# Macropad.net
KiCad netlist of a schematic drawn in Altium Designer
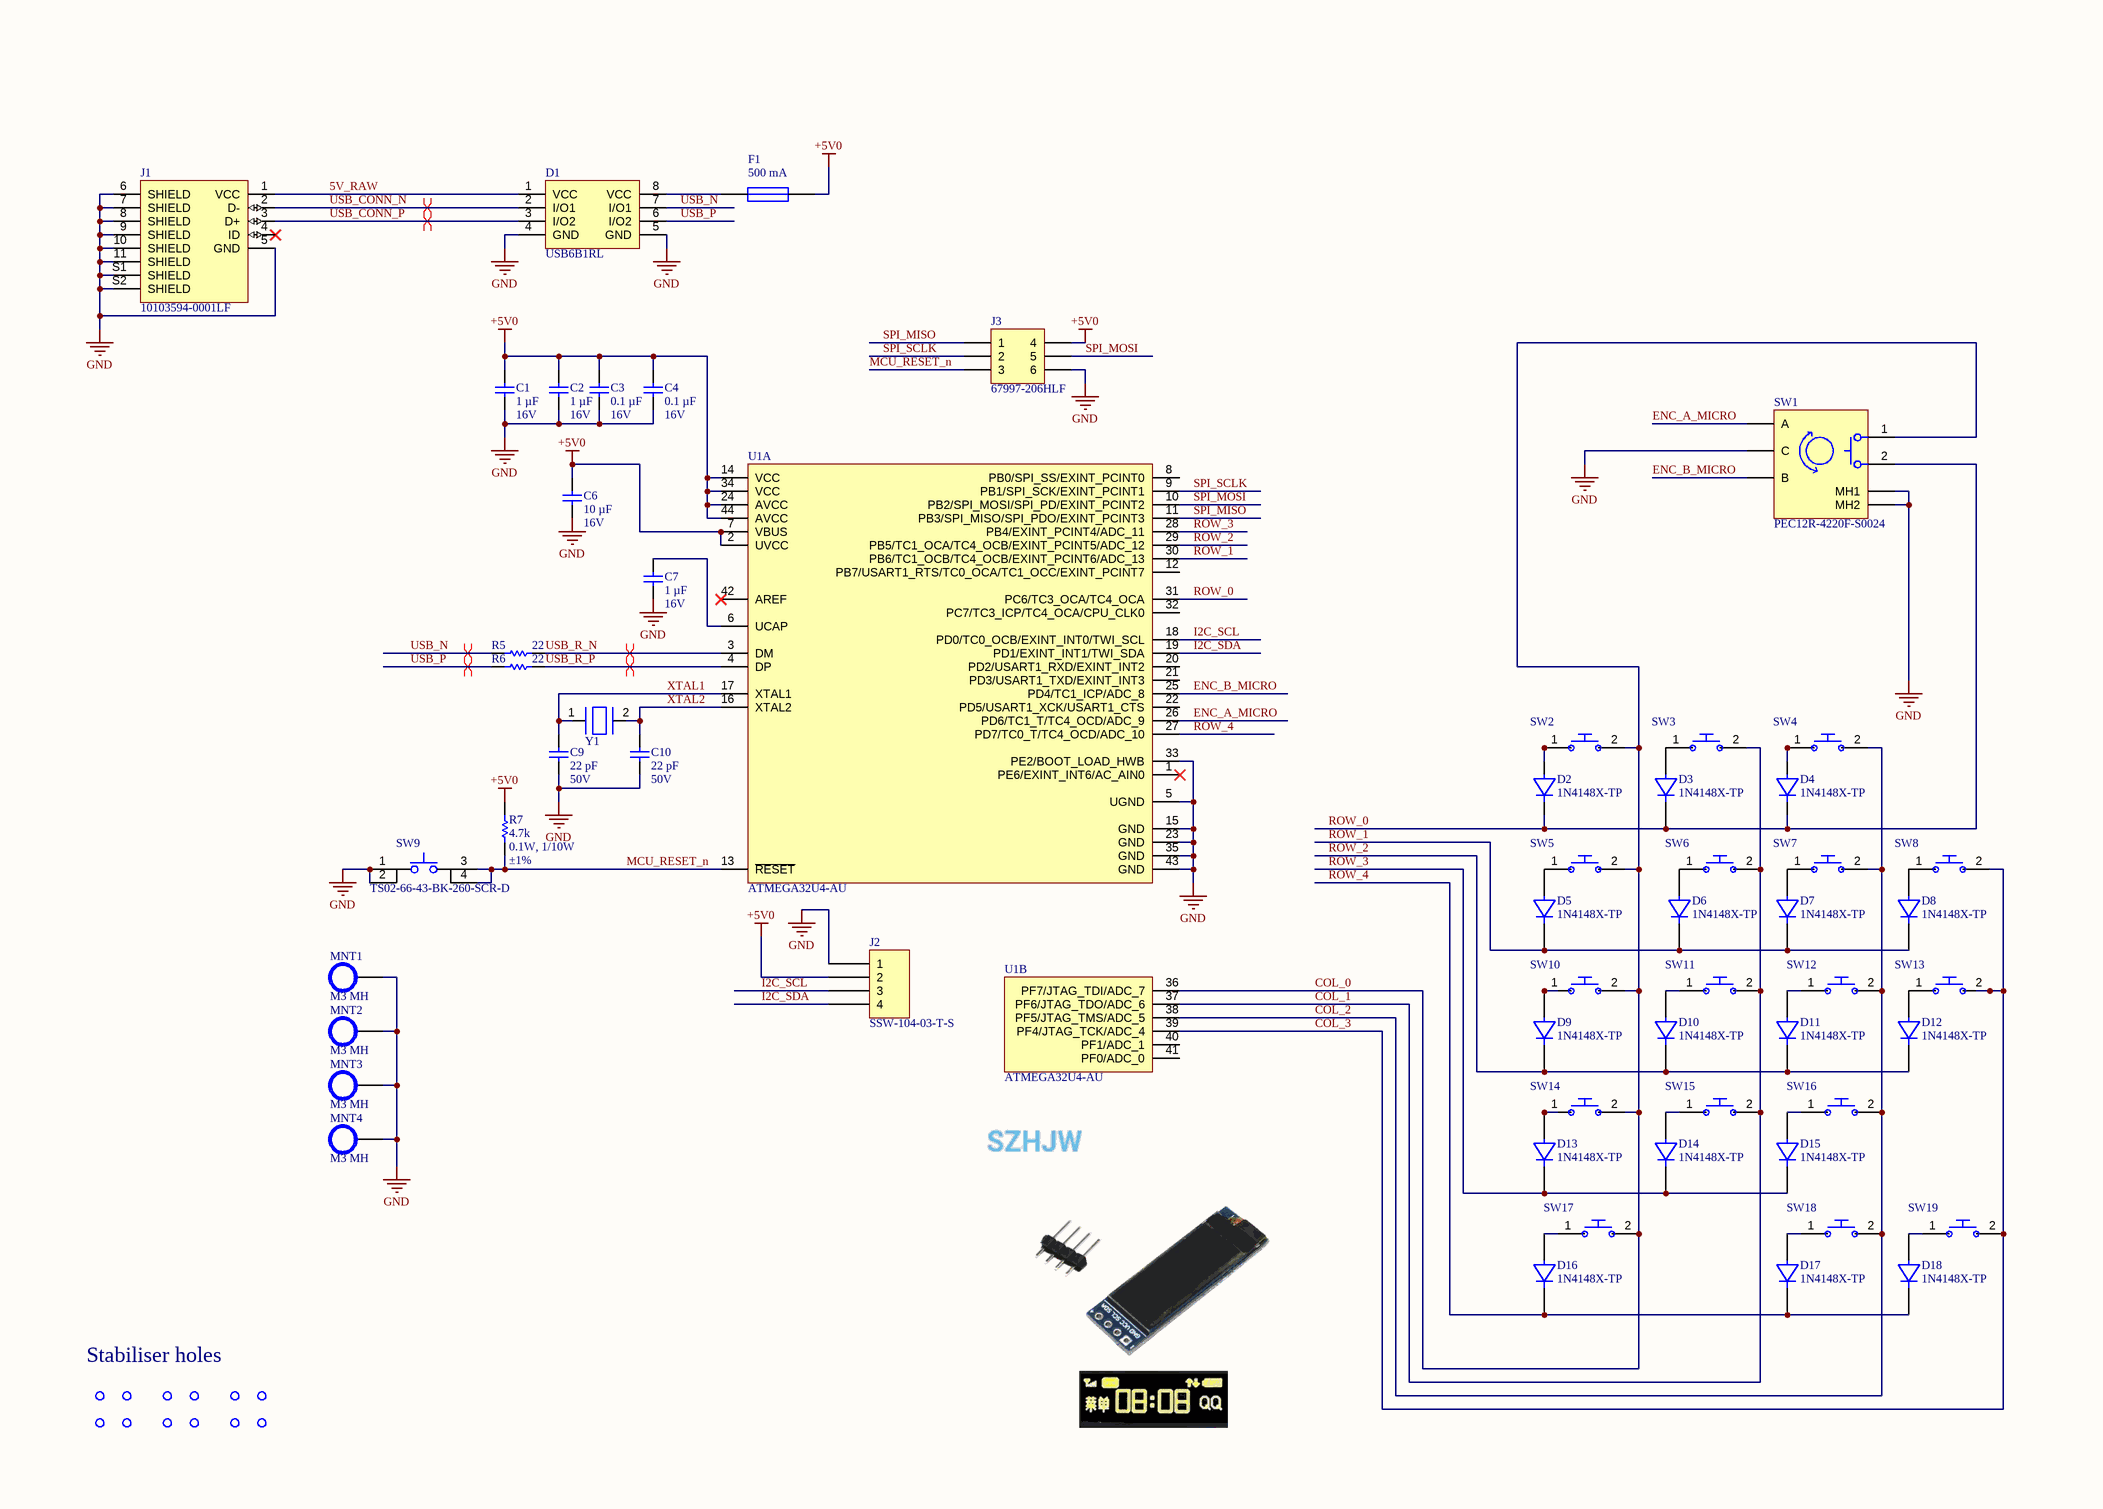
[diagram p0: Macropad.SchDoc]

(export (version "E")
  (design (tool "Eeschema 10.0.6"))
  (components
    (comp (ref "C1")
      (value "0603YC105KAT2A")
      (footprint "C_1608_0603")
      (description "CAP CER 1UF 16V X7R 0603")
      (fields
        (field (name "CAPACITANCE") "1 µF")
        (field (name "VOLTAGE RATING") "16V")
        (field (name "MANUFACTURER") "KYOCERA AVX")
        (field (name "TOLERANCE") "±10%")
      )
      (libsource (lib "adrianna-altium-lib") (part "C_NON_POLAR"))
    )
    (comp (ref "C2")
      (value "0603YC105KAT2A")
      (footprint "C_1608_0603")
      (description "CAP CER 1UF 16V X7R 0603")
      (fields
        (field (name "CAPACITANCE") "1 µF")
        (field (name "VOLTAGE RATING") "16V")
        (field (name "MANUFACTURER") "KYOCERA AVX")
        (field (name "TOLERANCE") "±10%")
      )
      (libsource (lib "adrianna-altium-lib") (part "C_NON_POLAR"))
    )
    (comp (ref "C3")
      (value "0603YC104KAT2A")
      (footprint "C_1608_0603")
      (description "CAP CER 0.1UF 16V X7R 0603")
      (fields
        (field (name "CAPACITANCE") "0.1 µF")
        (field (name "VOLTAGE RATING") "16V")
        (field (name "MANUFACTURER") "KYOCERA AVX")
        (field (name "TOLERANCE") "±10%")
      )
      (libsource (lib "adrianna-altium-lib") (part "C_NON_POLAR"))
    )
    (comp (ref "C4")
      (value "0603YC104KAT2A")
      (footprint "C_1608_0603")
      (description "CAP CER 0.1UF 16V X7R 0603")
      (fields
        (field (name "CAPACITANCE") "0.1 µF")
        (field (name "VOLTAGE RATING") "16V")
        (field (name "MANUFACTURER") "KYOCERA AVX")
        (field (name "TOLERANCE") "±10%")
      )
      (libsource (lib "adrianna-altium-lib") (part "C_NON_POLAR"))
    )
    (comp (ref "C6")
      (value "0805YC106KAT2A")
      (footprint "C_2012_0805")
      (description "CAP MLCC 10UF 16V 0805")
      (fields
        (field (name "CAPACITANCE") "10 µF")
        (field (name "VOLTAGE RATING") "16V")
        (field (name "MANUFACTURER") "KYOCERA AVX")
        (field (name "TOLERANCE") "±10%")
      )
      (libsource (lib "adrianna-altium-lib") (part "C_NON_POLAR"))
    )
    (comp (ref "C7")
      (value "0603YC105KAT2A")
      (footprint "C_1608_0603")
      (description "CAP CER 1UF 16V X7R 0603")
      (fields
        (field (name "CAPACITANCE") "1 µF")
        (field (name "VOLTAGE RATING") "16V")
        (field (name "MANUFACTURER") "KYOCERA AVX")
        (field (name "TOLERANCE") "±10%")
      )
      (libsource (lib "adrianna-altium-lib") (part "C_NON_POLAR"))
    )
    (comp (ref "C9")
      (value "06035A220JAT2A")
      (footprint "C_1608_0603")
      (description "CAP CER 22PF 50V C0G/NP0 0603")
      (fields
        (field (name "CAPACITANCE") "22 pF")
        (field (name "VOLTAGE RATING") "50V")
        (field (name "MANUFACTURER") "KYOCERA AVX")
        (field (name "TOLERANCE") "±5%")
      )
      (libsource (lib "adrianna-altium-lib") (part "C_NON_POLAR"))
    )
    (comp (ref "C10")
      (value "06035A220JAT2A")
      (footprint "C_1608_0603")
      (description "CAP CER 22PF 50V C0G/NP0 0603")
      (fields
        (field (name "CAPACITANCE") "22 pF")
        (field (name "VOLTAGE RATING") "50V")
        (field (name "MANUFACTURER") "KYOCERA AVX")
        (field (name "TOLERANCE") "±5%")
      )
      (libsource (lib "adrianna-altium-lib") (part "C_NON_POLAR"))
    )
    (comp (ref "D1")
      (value "USB6B1RL")
      (footprint "SOIC_8_1270_4900X3900X1750_ST_SO-8")
      (description "TVS DIODE 5.25VWM 8-SO")
      (fields (field (name "PN") "USB6B1RL") (field (name "MANUFACTURER") "STMicroelectronics"))
      (libsource (lib "adrianna-altium-lib") (part "D_TVS_USB6B1"))
    )
    (comp (ref "D2")
      (value "1N4148X-TP")
      (footprint "D_MCC_SOD-523")
      (description "DIODE GEN PURP 75V 150MA SOD523")
      (fields (field (name "MANUFACTURER") "Micro Commercial Co"))
      (libsource (lib "adrianna-altium-lib") (part "D_DIODE_KA"))
    )
    (comp (ref "D3")
      (value "1N4148X-TP")
      (footprint "D_MCC_SOD-523")
      (description "DIODE GEN PURP 75V 150MA SOD523")
      (fields (field (name "MANUFACTURER") "Micro Commercial Co"))
      (libsource (lib "adrianna-altium-lib") (part "D_DIODE_KA"))
    )
    (comp (ref "D4")
      (value "1N4148X-TP")
      (footprint "D_MCC_SOD-523")
      (description "DIODE GEN PURP 75V 150MA SOD523")
      (fields (field (name "MANUFACTURER") "Micro Commercial Co"))
      (libsource (lib "adrianna-altium-lib") (part "D_DIODE_KA"))
    )
    (comp (ref "D5")
      (value "1N4148X-TP")
      (footprint "D_MCC_SOD-523")
      (description "DIODE GEN PURP 75V 150MA SOD523")
      (fields (field (name "MANUFACTURER") "Micro Commercial Co"))
      (libsource (lib "adrianna-altium-lib") (part "D_DIODE_KA"))
    )
    (comp (ref "D6")
      (value "1N4148X-TP")
      (footprint "D_MCC_SOD-523")
      (description "DIODE GEN PURP 75V 150MA SOD523")
      (fields (field (name "MANUFACTURER") "Micro Commercial Co"))
      (libsource (lib "adrianna-altium-lib") (part "D_DIODE_KA"))
    )
    (comp (ref "D7")
      (value "1N4148X-TP")
      (footprint "D_MCC_SOD-523")
      (description "DIODE GEN PURP 75V 150MA SOD523")
      (fields (field (name "MANUFACTURER") "Micro Commercial Co"))
      (libsource (lib "adrianna-altium-lib") (part "D_DIODE_KA"))
    )
    (comp (ref "D8")
      (value "1N4148X-TP")
      (footprint "D_MCC_SOD-523")
      (description "DIODE GEN PURP 75V 150MA SOD523")
      (fields (field (name "MANUFACTURER") "Micro Commercial Co"))
      (libsource (lib "adrianna-altium-lib") (part "D_DIODE_KA"))
    )
    (comp (ref "D9")
      (value "1N4148X-TP")
      (footprint "D_MCC_SOD-523")
      (description "DIODE GEN PURP 75V 150MA SOD523")
      (fields (field (name "MANUFACTURER") "Micro Commercial Co"))
      (libsource (lib "adrianna-altium-lib") (part "D_DIODE_KA"))
    )
    (comp (ref "D10")
      (value "1N4148X-TP")
      (footprint "D_MCC_SOD-523")
      (description "DIODE GEN PURP 75V 150MA SOD523")
      (fields (field (name "MANUFACTURER") "Micro Commercial Co"))
      (libsource (lib "adrianna-altium-lib") (part "D_DIODE_KA"))
    )
    (comp (ref "D11")
      (value "1N4148X-TP")
      (footprint "D_MCC_SOD-523")
      (description "DIODE GEN PURP 75V 150MA SOD523")
      (fields (field (name "MANUFACTURER") "Micro Commercial Co"))
      (libsource (lib "adrianna-altium-lib") (part "D_DIODE_KA"))
    )
    (comp (ref "D12")
      (value "1N4148X-TP")
      (footprint "D_MCC_SOD-523")
      (description "DIODE GEN PURP 75V 150MA SOD523")
      (fields (field (name "MANUFACTURER") "Micro Commercial Co"))
      (libsource (lib "adrianna-altium-lib") (part "D_DIODE_KA"))
    )
    (comp (ref "D13")
      (value "1N4148X-TP")
      (footprint "D_MCC_SOD-523")
      (description "DIODE GEN PURP 75V 150MA SOD523")
      (fields (field (name "MANUFACTURER") "Micro Commercial Co"))
      (libsource (lib "adrianna-altium-lib") (part "D_DIODE_KA"))
    )
    (comp (ref "D14")
      (value "1N4148X-TP")
      (footprint "D_MCC_SOD-523")
      (description "DIODE GEN PURP 75V 150MA SOD523")
      (fields (field (name "MANUFACTURER") "Micro Commercial Co"))
      (libsource (lib "adrianna-altium-lib") (part "D_DIODE_KA"))
    )
    (comp (ref "D15")
      (value "1N4148X-TP")
      (footprint "D_MCC_SOD-523")
      (description "DIODE GEN PURP 75V 150MA SOD523")
      (fields (field (name "MANUFACTURER") "Micro Commercial Co"))
      (libsource (lib "adrianna-altium-lib") (part "D_DIODE_KA"))
    )
    (comp (ref "D16")
      (value "1N4148X-TP")
      (footprint "D_MCC_SOD-523")
      (description "DIODE GEN PURP 75V 150MA SOD523")
      (fields (field (name "MANUFACTURER") "Micro Commercial Co"))
      (libsource (lib "adrianna-altium-lib") (part "D_DIODE_KA"))
    )
    (comp (ref "D17")
      (value "1N4148X-TP")
      (footprint "D_MCC_SOD-523")
      (description "DIODE GEN PURP 75V 150MA SOD523")
      (fields (field (name "MANUFACTURER") "Micro Commercial Co"))
      (libsource (lib "adrianna-altium-lib") (part "D_DIODE_KA"))
    )
    (comp (ref "D18")
      (value "1N4148X-TP")
      (footprint "D_MCC_SOD-523")
      (description "DIODE GEN PURP 75V 150MA SOD523")
      (fields (field (name "MANUFACTURER") "Micro Commercial Co"))
      (libsource (lib "adrianna-altium-lib") (part "D_DIODE_KA"))
    )
    (comp (ref "F1")
      (value "0ZCK0050FF2E")
      (footprint "FUSE_2012_0805_BELFUSE")
      (description "PTC RESET FUSE 6V 500MA 0805")
      (fields (field (name "MANUFACTURER") "Bel Fuse Inc.") (field (name "CURRENT RATING") "500 mA"))
      (libsource (lib "adrianna-altium-lib") (part "F_FUSE"))
    )
    (comp (ref "J1")
      (value "10103594-0001LF")
      (footprint "CONN_10103594-0001LF")
      (description "CONN RCPT USB2.0 MICRO B SMD R/A")
      (fields (field (name "PN") "10103594-0001LF") (field (name "MANUFACTURER") "Amphenol ICC (FCI)"))
      (libsource (lib "adrianna-altium-lib") (part "J_CONN_MICRO-USB"))
    )
    (comp (ref "J2")
      (value "SSW-104-03-T-S")
      (footprint "SAMTEC SSW-104-03-T-S")
      (description "CONN RCPT 4POS 0.1 TIN PCB")
      (fields (field (name "MANUFACTURER") "Samtec Inc."))
      (libsource (lib "Celestial Altium Library - altium_library") (part "4 Pin"))
    )
    (comp (ref "J3")
      (value "67997-206HLF")
      (footprint "CONN_2X3_HDR_2540")
      (description "CONN HEADER VERT 6POS 2.54MM")
      (fields (field (name "PN") "67997-206HLF") (field (name "MANUFACTURER") "Amphenol ICC (FCI)"))
      (libsource (lib "adrianna-altium-lib") (part "J_HDR_2X3"))
    )
    (comp (ref "MNT1")
      (value "M3 Mounting Hole")
      (footprint "MH_M3_PTH_VIA-SPOKES")
      (fields (field (name "DISPLAY NAME") "M3 MH"))
      (libsource (lib "adrianna-altium-lib") (part "MH_M3"))
    )
    (comp (ref "MNT2")
      (value "M3 Mounting Hole")
      (footprint "MH_M3_PTH_VIA-SPOKES")
      (fields (field (name "DISPLAY NAME") "M3 MH"))
      (libsource (lib "adrianna-altium-lib") (part "MH_M3"))
    )
    (comp (ref "MNT3")
      (value "M3 Mounting Hole")
      (footprint "MH_M3_PTH_VIA-SPOKES")
      (fields (field (name "DISPLAY NAME") "M3 MH"))
      (libsource (lib "adrianna-altium-lib") (part "MH_M3"))
    )
    (comp (ref "MNT4")
      (value "M3 Mounting Hole")
      (footprint "MH_M3_PTH_VIA-SPOKES")
      (fields (field (name "DISPLAY NAME") "M3 MH"))
      (libsource (lib "adrianna-altium-lib") (part "MH_M3"))
    )
    (comp (ref "R5")
      (value "RMCF0603FT22R0")
      (footprint "R_1608_0603")
      (description "RES 22 OHM 1% 1/10W 0603")
      (fields
        (field (name "RESISTANCE") "22")
        (field (name "MANUFACTURER") "Stackpole Electronics Inc")
        (field (name "TOLERANCE") "±1%")
      )
      (libsource (lib "adrianna-altium-lib") (part "R_RESISTOR"))
    )
    (comp (ref "R6")
      (value "RMCF0603FT22R0")
      (footprint "R_1608_0603")
      (description "RES 22 OHM 1% 1/10W 0603")
      (fields
        (field (name "RESISTANCE") "22")
        (field (name "MANUFACTURER") "Stackpole Electronics Inc")
        (field (name "TOLERANCE") "±1%")
      )
      (libsource (lib "adrianna-altium-lib") (part "R_RESISTOR"))
    )
    (comp (ref "R7")
      (value "RMCF0603FT4K70")
      (footprint "R_1608_0603")
      (description "RES 4.7K OHM 1% 1/10W 0603")
      (fields
        (field (name "RESISTANCE") "4.7k")
        (field (name "POWER RATING") "0.1W, 1/10W")
        (field (name "MANUFACTURER") "Stackpole Electronics Inc")
        (field (name "TOLERANCE") "±1%")
      )
      (libsource (lib "adrianna-altium-lib") (part "R_RESISTOR"))
    )
    (comp (ref "STAB1")
      (value "Cherry Stabiliser Hole")
      (footprint "HOLE_CHERRY_STAB")
      (libsource (lib "adrianna-altium-lib") (part "HOLE_4"))
    )
    (comp (ref "STAB2")
      (value "Cherry Stabiliser Hole")
      (footprint "HOLE_CHERRY_STAB")
      (libsource (lib "adrianna-altium-lib") (part "HOLE_4"))
    )
    (comp (ref "STAB3")
      (value "Cherry Stabiliser Hole")
      (footprint "HOLE_CHERRY_STAB")
      (libsource (lib "adrianna-altium-lib") (part "HOLE_4"))
    )
    (comp (ref "SW1")
      (value "PEC12R-4220F-S0024")
      (footprint "SW_ENCODER_PEC12R-4220F-S0024")
      (description "ROTARY ENCODER MECHANICAL 24PPR")
      (fields (field (name "MANUFACTURER") "Bourns Inc."))
      (libsource (lib "adrianna-altium-lib") (part "SW_ENCODER_PEC12R-4220F-S0024"))
    )
    (comp (ref "SW2")
      (value "MX-Style Switch")
      (footprint "SW_CHERRY-MX-STYLE")
      (libsource (lib "adrianna-altium-lib") (part "SW_TACTILE_2POS"))
    )
    (comp (ref "SW3")
      (value "MX-Style Switch")
      (footprint "SW_CHERRY-MX-STYLE")
      (libsource (lib "adrianna-altium-lib") (part "SW_TACTILE_2POS"))
    )
    (comp (ref "SW4")
      (value "MX-Style Switch")
      (footprint "SW_CHERRY-MX-STYLE")
      (libsource (lib "adrianna-altium-lib") (part "SW_TACTILE_2POS"))
    )
    (comp (ref "SW5")
      (value "MX-Style Switch")
      (footprint "SW_CHERRY-MX-STYLE")
      (libsource (lib "adrianna-altium-lib") (part "SW_TACTILE_2POS"))
    )
    (comp (ref "SW6")
      (value "MX-Style Switch")
      (footprint "SW_CHERRY-MX-STYLE")
      (libsource (lib "adrianna-altium-lib") (part "SW_TACTILE_2POS"))
    )
    (comp (ref "SW7")
      (value "MX-Style Switch")
      (footprint "SW_CHERRY-MX-STYLE")
      (libsource (lib "adrianna-altium-lib") (part "SW_TACTILE_2POS"))
    )
    (comp (ref "SW8")
      (value "MX-Style Switch")
      (footprint "SW_CHERRY-MX-STYLE")
      (libsource (lib "adrianna-altium-lib") (part "SW_TACTILE_2POS"))
    )
    (comp (ref "SW9")
      (value "TS02-66-43-BK-260-SCR-D")
      (footprint "TS02-66-43-BK-260-SCR-D")
      (libsource (lib "Macropad") (part "TS02-66-43-BK-260-SCR-D"))
    )
    (comp (ref "SW10")
      (value "MX-Style Switch")
      (footprint "SW_CHERRY-MX-STYLE")
      (libsource (lib "adrianna-altium-lib") (part "SW_TACTILE_2POS"))
    )
    (comp (ref "SW11")
      (value "MX-Style Switch")
      (footprint "SW_CHERRY-MX-STYLE")
      (libsource (lib "adrianna-altium-lib") (part "SW_TACTILE_2POS"))
    )
    (comp (ref "SW12")
      (value "MX-Style Switch")
      (footprint "SW_CHERRY-MX-STYLE")
      (libsource (lib "adrianna-altium-lib") (part "SW_TACTILE_2POS"))
    )
    (comp (ref "SW13")
      (value "MX-Style Switch")
      (footprint "SW_CHERRY-MX-STYLE")
      (libsource (lib "adrianna-altium-lib") (part "SW_TACTILE_2POS"))
    )
    (comp (ref "SW14")
      (value "MX-Style Switch")
      (footprint "SW_CHERRY-MX-STYLE")
      (libsource (lib "adrianna-altium-lib") (part "SW_TACTILE_2POS"))
    )
    (comp (ref "SW15")
      (value "MX-Style Switch")
      (footprint "SW_CHERRY-MX-STYLE")
      (libsource (lib "adrianna-altium-lib") (part "SW_TACTILE_2POS"))
    )
    (comp (ref "SW16")
      (value "MX-Style Switch")
      (footprint "SW_CHERRY-MX-STYLE")
      (libsource (lib "adrianna-altium-lib") (part "SW_TACTILE_2POS"))
    )
    (comp (ref "SW17")
      (value "MX-Style Switch")
      (footprint "SW_CHERRY-MX-STYLE")
      (libsource (lib "adrianna-altium-lib") (part "SW_TACTILE_2POS"))
    )
    (comp (ref "SW18")
      (value "MX-Style Switch")
      (footprint "SW_CHERRY-MX-STYLE")
      (libsource (lib "adrianna-altium-lib") (part "SW_TACTILE_2POS"))
    )
    (comp (ref "SW19")
      (value "MX-Style Switch")
      (footprint "SW_CHERRY-MX-STYLE")
      (libsource (lib "adrianna-altium-lib") (part "SW_TACTILE_2POS"))
    )
    (comp (ref "U1")
      (value "ATMEGA32U4-AU")
      (footprint "QFP_44_800_1200X1200X120_ATMEL")
      (description "IC MCU 8BIT 32KB FLASH 44TQFP")
      (fields (field (name "MANUFACTURER") "Microchip Technology"))
      (libsource (lib "adrianna-altium-lib") (part "U_MCU_ATMEGA32U4"))
    )
    (comp (ref "Y1")
      (value "830036034")
      (footprint "Y_XTAL_HC49")
      (description "WE-XTAL QUARTZ CRYSTAL 16.0 MHZ;")
      (fields (field (name "MANUFACTURER") "Würth Elektronik"))
      (libsource (lib "adrianna-altium-lib") (part "Y_XTAL_X1X2"))
    )
  )
  (nets
    (net (code "1") (name "+5V0") (class "Default")
      (node (ref "C1") (pin "2") (pinfunction "2_2") (pintype "passive"))
      (node (ref "C2") (pin "2") (pinfunction "2_2") (pintype "passive"))
      (node (ref "C3") (pin "2") (pinfunction "2_2") (pintype "passive"))
      (node (ref "C4") (pin "2") (pinfunction "2_2") (pintype "passive"))
      (node (ref "C6") (pin "2") (pinfunction "2_2") (pintype "passive"))
      (node (ref "F1") (pin "2") (pinfunction "2_2") (pintype "passive"))
      (node (ref "J2") (pin "2") (pinfunction "2_2") (pintype "passive"))
      (node (ref "J3") (pin "4") (pinfunction "4_4") (pintype "passive"))
      (node (ref "R7") (pin "2") (pinfunction "2_2") (pintype "passive"))
      (node (ref "U1") (pin "14") (pinfunction "VCC_14") (pintype "passive"))
      (node (ref "U1") (pin "2") (pinfunction "UVCC_2") (pintype "passive"))
      (node (ref "U1") (pin "24") (pinfunction "AVCC_24") (pintype "passive"))
      (node (ref "U1") (pin "34") (pinfunction "VCC_34") (pintype "passive"))
      (node (ref "U1") (pin "44") (pinfunction "AVCC_44") (pintype "passive"))
      (node (ref "U1") (pin "7") (pinfunction "VBUS_7") (pintype "passive"))
    )
    (net (code "2") (name "/5V_RAW") (class "Default")
      (node (ref "D1") (pin "1") (pinfunction "VCC_1") (pintype "passive"))
      (node (ref "J1") (pin "1") (pinfunction "VCC_1") (pintype "power_in"))
    )
    (net (code "4") (name "/COL_0") (class "Default")
      (node (ref "SW1") (pin "1") (pinfunction "1_1") (pintype "passive"))
      (node (ref "SW10") (pin "2") (pinfunction "2_2") (pintype "passive"))
      (node (ref "SW14") (pin "2") (pinfunction "2_2") (pintype "passive"))
      (node (ref "SW17") (pin "2") (pinfunction "2_2") (pintype "passive"))
      (node (ref "SW2") (pin "2") (pinfunction "2_2") (pintype "passive"))
      (node (ref "SW5") (pin "2") (pinfunction "2_2") (pintype "passive"))
      (node (ref "U1") (pin "36") (pinfunction "PF7/JTAG_TDI/ADC_7_36") (pintype "passive"))
    )
    (net (code "5") (name "/COL_1") (class "Default")
      (node (ref "SW11") (pin "2") (pinfunction "2_2") (pintype "passive"))
      (node (ref "SW15") (pin "2") (pinfunction "2_2") (pintype "passive"))
      (node (ref "SW3") (pin "2") (pinfunction "2_2") (pintype "passive"))
      (node (ref "SW6") (pin "2") (pinfunction "2_2") (pintype "passive"))
      (node (ref "U1") (pin "37") (pinfunction "PF6/JTAG_TDO/ADC_6_37") (pintype "passive"))
    )
    (net (code "6") (name "/COL_2") (class "Default")
      (node (ref "SW12") (pin "2") (pinfunction "2_2") (pintype "passive"))
      (node (ref "SW16") (pin "2") (pinfunction "2_2") (pintype "passive"))
      (node (ref "SW18") (pin "2") (pinfunction "2_2") (pintype "passive"))
      (node (ref "SW4") (pin "2") (pinfunction "2_2") (pintype "passive"))
      (node (ref "SW7") (pin "2") (pinfunction "2_2") (pintype "passive"))
      (node (ref "U1") (pin "38") (pinfunction "PF5/JTAG_TMS/ADC_5_38") (pintype "passive"))
    )
    (net (code "7") (name "/COL_3") (class "Default")
      (node (ref "SW13") (pin "2") (pinfunction "2_2") (pintype "passive"))
      (node (ref "SW19") (pin "2") (pinfunction "2_2") (pintype "passive"))
      (node (ref "SW8") (pin "2") (pinfunction "2_2") (pintype "passive"))
      (node (ref "U1") (pin "39") (pinfunction "PF4/JTAG_TCK/ADC_4_39") (pintype "passive"))
    )
    (net (code "8") (name "/ENC_A_MICRO") (class "Default")
      (node (ref "SW1") (pin "A") (pinfunction "A_A") (pintype "passive"))
      (node (ref "U1") (pin "26") (pinfunction "PD6/TC1_T/TC4_OCD/ADC_9_26") (pintype "passive"))
    )
    (net (code "9") (name "/ENC_B_MICRO") (class "Default")
      (node (ref "SW1") (pin "B") (pinfunction "B_B") (pintype "passive"))
      (node (ref "U1") (pin "25") (pinfunction "PD4/TC1_ICP/ADC_8_25") (pintype "passive"))
    )
    (net (code "10") (name "/I2C_SCL") (class "Default")
      (node (ref "J2") (pin "3") (pinfunction "3_3") (pintype "passive"))
      (node (ref "U1") (pin "18") (pinfunction "PD0/TC0_OCB/EXINT_INT0/TWI_SCL_18") (pintype "passive"))
    )
    (net (code "11") (name "/I2C_SDA") (class "Default")
      (node (ref "J2") (pin "4") (pinfunction "4_4") (pintype "passive"))
      (node (ref "U1") (pin "19") (pinfunction "PD1/EXINT_INT1/TWI_SDA_19") (pintype "passive"))
    )
    (net (code "12") (name "/MCU_RESET_n") (class "Default")
      (node (ref "J3") (pin "3") (pinfunction "3_3") (pintype "passive"))
      (node (ref "R7") (pin "1") (pinfunction "1_1") (pintype "passive"))
      (node (ref "SW9") (pin "3") (pinfunction "3_3") (pintype "passive"))
      (node (ref "SW9") (pin "4") (pinfunction "4_4") (pintype "passive"))
      (node (ref "U1") (pin "13") (pinfunction "~{RESET}_13") (pintype "passive"))
    )
    (net (code "13") (name "/ROW_0") (class "Default")
      (node (ref "D2") (pin "1") (pinfunction "Cathode_1") (pintype "passive"))
      (node (ref "D3") (pin "1") (pinfunction "Cathode_1") (pintype "passive"))
      (node (ref "D4") (pin "1") (pinfunction "Cathode_1") (pintype "passive"))
      (node (ref "SW1") (pin "2") (pinfunction "2_2") (pintype "passive"))
      (node (ref "U1") (pin "31") (pinfunction "PC6/TC3_OCA/TC4_OCA_31") (pintype "passive"))
    )
    (net (code "14") (name "/ROW_1") (class "Default")
      (node (ref "D5") (pin "1") (pinfunction "Cathode_1") (pintype "passive"))
      (node (ref "D6") (pin "1") (pinfunction "Cathode_1") (pintype "passive"))
      (node (ref "D7") (pin "1") (pinfunction "Cathode_1") (pintype "passive"))
      (node (ref "D8") (pin "1") (pinfunction "Cathode_1") (pintype "passive"))
      (node (ref "U1") (pin "30") (pinfunction "PB6/TC1_OCB/TC4_OCB/EXINT_PCINT6/ADC_13_30") (pintype "passive"))
    )
    (net (code "15") (name "/ROW_2") (class "Default")
      (node (ref "D10") (pin "1") (pinfunction "Cathode_1") (pintype "passive"))
      (node (ref "D11") (pin "1") (pinfunction "Cathode_1") (pintype "passive"))
      (node (ref "D12") (pin "1") (pinfunction "Cathode_1") (pintype "passive"))
      (node (ref "D9") (pin "1") (pinfunction "Cathode_1") (pintype "passive"))
      (node (ref "U1") (pin "29") (pinfunction "PB5/TC1_OCA/TC4_OCB/EXINT_PCINT5/ADC_12_29") (pintype "passive"))
    )
    (net (code "16") (name "/ROW_3") (class "Default")
      (node (ref "D13") (pin "1") (pinfunction "Cathode_1") (pintype "passive"))
      (node (ref "D14") (pin "1") (pinfunction "Cathode_1") (pintype "passive"))
      (node (ref "D15") (pin "1") (pinfunction "Cathode_1") (pintype "passive"))
      (node (ref "U1") (pin "28") (pinfunction "PB4/EXINT_PCINT4/ADC_11_28") (pintype "passive"))
    )
    (net (code "17") (name "/ROW_4") (class "Default")
      (node (ref "D16") (pin "1") (pinfunction "Cathode_1") (pintype "passive"))
      (node (ref "D17") (pin "1") (pinfunction "Cathode_1") (pintype "passive"))
      (node (ref "D18") (pin "1") (pinfunction "Cathode_1") (pintype "passive"))
      (node (ref "U1") (pin "27") (pinfunction "PD7/TC0_T/TC4_OCD/ADC_10_27") (pintype "passive"))
    )
    (net (code "18") (name "/SPI_MISO") (class "Default")
      (node (ref "J3") (pin "1") (pinfunction "1_1") (pintype "passive"))
      (node (ref "U1") (pin "11") (pinfunction "PB3/SPI_MISO/SPI_PDO/EXINT_PCINT3_11") (pintype "passive"))
    )
    (net (code "19") (name "/SPI_MOSI") (class "Default")
      (node (ref "J3") (pin "5") (pinfunction "5_5") (pintype "passive"))
      (node (ref "U1") (pin "10") (pinfunction "PB2/SPI_MOSI/SPI_PD/EXINT_PCINT2_10") (pintype "passive"))
    )
    (net (code "20") (name "/SPI_SCLK") (class "Default")
      (node (ref "J3") (pin "2") (pinfunction "2_2") (pintype "passive"))
      (node (ref "U1") (pin "9") (pinfunction "PB1/SPI_SCK/EXINT_PCINT1_9") (pintype "passive"))
    )
    (net (code "21") (name "/USB_CONN_N") (class "Default")
      (node (ref "D1") (pin "2") (pinfunction "I/O1_2") (pintype "passive"))
      (node (ref "J1") (pin "2") (pinfunction "D-_2") (pintype "bidirectional"))
    )
    (net (code "22") (name "/USB_CONN_P") (class "Default")
      (node (ref "D1") (pin "3") (pinfunction "I/O2_3") (pintype "passive"))
      (node (ref "J1") (pin "3") (pinfunction "D+_3") (pintype "bidirectional"))
    )
    (net (code "23") (name "/USB_N") (class "Default")
      (node (ref "D1") (pin "7") (pinfunction "I/O1_7") (pintype "passive"))
      (node (ref "R5") (pin "1") (pinfunction "1_1") (pintype "passive"))
    )
    (net (code "24") (name "/USB_P") (class "Default")
      (node (ref "D1") (pin "6") (pinfunction "I/O2_6") (pintype "passive"))
      (node (ref "R6") (pin "1") (pinfunction "1_1") (pintype "passive"))
    )
    (net (code "25") (name "/USB_R_N") (class "Default")
      (node (ref "R5") (pin "2") (pinfunction "2_2") (pintype "passive"))
      (node (ref "U1") (pin "3") (pinfunction "DM_3") (pintype "passive"))
    )
    (net (code "26") (name "/USB_R_P") (class "Default")
      (node (ref "R6") (pin "2") (pinfunction "2_2") (pintype "passive"))
      (node (ref "U1") (pin "4") (pinfunction "DP_4") (pintype "passive"))
    )
    (net (code "27") (name "/XTAL1") (class "Default")
      (node (ref "C9") (pin "1") (pinfunction "1_1") (pintype "passive"))
      (node (ref "U1") (pin "17") (pinfunction "XTAL1_17") (pintype "passive"))
      (node (ref "Y1") (pin "1") (pinfunction "1_1") (pintype "passive"))
    )
    (net (code "28") (name "/XTAL2") (class "Default")
      (node (ref "C10") (pin "1") (pinfunction "1_1") (pintype "passive"))
      (node (ref "U1") (pin "16") (pinfunction "XTAL2_16") (pintype "passive"))
      (node (ref "Y1") (pin "2") (pinfunction "2_2") (pintype "passive"))
    )
    (net (code "29") (name "GND") (class "Default")
      (node (ref "C1") (pin "1") (pinfunction "1_1") (pintype "passive"))
      (node (ref "C10") (pin "2") (pinfunction "2_2") (pintype "passive"))
      (node (ref "C2") (pin "1") (pinfunction "1_1") (pintype "passive"))
      (node (ref "C3") (pin "1") (pinfunction "1_1") (pintype "passive"))
      (node (ref "C4") (pin "1") (pinfunction "1_1") (pintype "passive"))
      (node (ref "C6") (pin "1") (pinfunction "1_1") (pintype "passive"))
      (node (ref "C7") (pin "1") (pinfunction "1_1") (pintype "passive"))
      (node (ref "C9") (pin "2") (pinfunction "2_2") (pintype "passive"))
      (node (ref "D1") (pin "4") (pinfunction "GND_4") (pintype "passive"))
      (node (ref "D1") (pin "5") (pinfunction "GND_5") (pintype "passive"))
      (node (ref "J1") (pin "10") (pinfunction "SHIELD_10") (pintype "passive"))
      (node (ref "J1") (pin "11") (pinfunction "SHIELD_11") (pintype "passive"))
      (node (ref "J1") (pin "5") (pinfunction "GND_5") (pintype "power_in"))
      (node (ref "J1") (pin "6") (pinfunction "SHIELD_6") (pintype "passive"))
      (node (ref "J1") (pin "7") (pinfunction "SHIELD_7") (pintype "passive"))
      (node (ref "J1") (pin "8") (pinfunction "SHIELD_8") (pintype "passive"))
      (node (ref "J1") (pin "9") (pinfunction "SHIELD_9") (pintype "passive"))
      (node (ref "J1") (pin "S1") (pinfunction "SHIELD_S1") (pintype "passive"))
      (node (ref "J1") (pin "S2") (pinfunction "SHIELD_S2") (pintype "passive"))
      (node (ref "J2") (pin "1") (pinfunction "1_1") (pintype "passive"))
      (node (ref "J3") (pin "6") (pinfunction "6_6") (pintype "passive"))
      (node (ref "MNT1") (pin "1") (pinfunction "1_1") (pintype "passive"))
      (node (ref "MNT2") (pin "1") (pinfunction "1_1") (pintype "passive"))
      (node (ref "MNT3") (pin "1") (pinfunction "1_1") (pintype "passive"))
      (node (ref "MNT4") (pin "1") (pinfunction "1_1") (pintype "passive"))
      (node (ref "SW1") (pin "C") (pinfunction "C_C") (pintype "passive"))
      (node (ref "SW1") (pin "MH1") (pinfunction "MH1_MH1") (pintype "passive"))
      (node (ref "SW1") (pin "MH2") (pinfunction "MH2_MH2") (pintype "passive"))
      (node (ref "SW9") (pin "1") (pinfunction "1_1") (pintype "passive"))
      (node (ref "SW9") (pin "2") (pinfunction "2_2") (pintype "passive"))
      (node (ref "U1") (pin "15") (pinfunction "GND_15") (pintype "passive"))
      (node (ref "U1") (pin "23") (pinfunction "GND_23") (pintype "passive"))
      (node (ref "U1") (pin "33") (pinfunction "PE2/BOOT_LOAD_HWB_33") (pintype "passive"))
      (node (ref "U1") (pin "35") (pinfunction "GND_35") (pintype "passive"))
      (node (ref "U1") (pin "43") (pinfunction "GND_43") (pintype "passive"))
      (node (ref "U1") (pin "5") (pinfunction "UGND_5") (pintype "passive"))
    )
    (net (code "30") (name "Net-(D1-VCC-Pad8)") (class "Default")
      (node (ref "D1") (pin "8") (pinfunction "VCC_8") (pintype "passive"))
      (node (ref "F1") (pin "1") (pinfunction "1_1") (pintype "passive"))
    )
    (net (code "31") (name "Net-(D2-Anode)") (class "Default")
      (node (ref "D2") (pin "2") (pinfunction "Anode_2") (pintype "passive"))
      (node (ref "SW2") (pin "1") (pinfunction "1_1") (pintype "passive"))
    )
    (net (code "32") (name "Net-(D3-Anode)") (class "Default")
      (node (ref "D3") (pin "2") (pinfunction "Anode_2") (pintype "passive"))
      (node (ref "SW3") (pin "1") (pinfunction "1_1") (pintype "passive"))
    )
    (net (code "33") (name "Net-(D4-Anode)") (class "Default")
      (node (ref "D4") (pin "2") (pinfunction "Anode_2") (pintype "passive"))
      (node (ref "SW4") (pin "1") (pinfunction "1_1") (pintype "passive"))
    )
    (net (code "34") (name "Net-(D5-Anode)") (class "Default")
      (node (ref "D5") (pin "2") (pinfunction "Anode_2") (pintype "passive"))
      (node (ref "SW5") (pin "1") (pinfunction "1_1") (pintype "passive"))
    )
    (net (code "35") (name "Net-(D6-Anode)") (class "Default")
      (node (ref "D6") (pin "2") (pinfunction "Anode_2") (pintype "passive"))
      (node (ref "SW6") (pin "1") (pinfunction "1_1") (pintype "passive"))
    )
    (net (code "36") (name "Net-(D7-Anode)") (class "Default")
      (node (ref "D7") (pin "2") (pinfunction "Anode_2") (pintype "passive"))
      (node (ref "SW7") (pin "1") (pinfunction "1_1") (pintype "passive"))
    )
    (net (code "37") (name "Net-(D8-Anode)") (class "Default")
      (node (ref "D8") (pin "2") (pinfunction "Anode_2") (pintype "passive"))
      (node (ref "SW8") (pin "1") (pinfunction "1_1") (pintype "passive"))
    )
    (net (code "38") (name "Net-(D9-Anode)") (class "Default")
      (node (ref "D9") (pin "2") (pinfunction "Anode_2") (pintype "passive"))
      (node (ref "SW10") (pin "1") (pinfunction "1_1") (pintype "passive"))
    )
    (net (code "39") (name "Net-(D10-Anode)") (class "Default")
      (node (ref "D10") (pin "2") (pinfunction "Anode_2") (pintype "passive"))
      (node (ref "SW11") (pin "1") (pinfunction "1_1") (pintype "passive"))
    )
    (net (code "40") (name "Net-(D11-Anode)") (class "Default")
      (node (ref "D11") (pin "2") (pinfunction "Anode_2") (pintype "passive"))
      (node (ref "SW12") (pin "1") (pinfunction "1_1") (pintype "passive"))
    )
    (net (code "41") (name "Net-(D12-Anode)") (class "Default")
      (node (ref "D12") (pin "2") (pinfunction "Anode_2") (pintype "passive"))
      (node (ref "SW13") (pin "1") (pinfunction "1_1") (pintype "passive"))
    )
    (net (code "42") (name "Net-(D13-Anode)") (class "Default")
      (node (ref "D13") (pin "2") (pinfunction "Anode_2") (pintype "passive"))
      (node (ref "SW14") (pin "1") (pinfunction "1_1") (pintype "passive"))
    )
    (net (code "43") (name "Net-(D14-Anode)") (class "Default")
      (node (ref "D14") (pin "2") (pinfunction "Anode_2") (pintype "passive"))
      (node (ref "SW15") (pin "1") (pinfunction "1_1") (pintype "passive"))
    )
    (net (code "44") (name "Net-(D15-Anode)") (class "Default")
      (node (ref "D15") (pin "2") (pinfunction "Anode_2") (pintype "passive"))
      (node (ref "SW16") (pin "1") (pinfunction "1_1") (pintype "passive"))
    )
    (net (code "45") (name "Net-(D16-Anode)") (class "Default")
      (node (ref "D16") (pin "2") (pinfunction "Anode_2") (pintype "passive"))
      (node (ref "SW17") (pin "1") (pinfunction "1_1") (pintype "passive"))
    )
    (net (code "46") (name "Net-(D17-Anode)") (class "Default")
      (node (ref "D17") (pin "2") (pinfunction "Anode_2") (pintype "passive"))
      (node (ref "SW18") (pin "1") (pinfunction "1_1") (pintype "passive"))
    )
    (net (code "47") (name "Net-(D18-Anode)") (class "Default")
      (node (ref "D18") (pin "2") (pinfunction "Anode_2") (pintype "passive"))
      (node (ref "SW19") (pin "1") (pinfunction "1_1") (pintype "passive"))
    )
    (net (code "48") (name "Net-(U1A-UCAP)") (class "Default")
      (node (ref "C7") (pin "2") (pinfunction "2_2") (pintype "passive"))
      (node (ref "U1") (pin "6") (pinfunction "UCAP_6") (pintype "passive"))
    )
    (net (code "49") (name "unconnected-(J1-ID-Pad4)") (class "Default")
      (node (ref "J1") (pin "4") (pinfunction "ID_4") (pintype "bidirectional+no_connect"))
    )
    (net (code "50") (name "unconnected-(U1A-AREF-Pad42)") (class "Default")
      (node (ref "U1") (pin "42") (pinfunction "AREF_42") (pintype "passive+no_connect"))
    )
    (net (code "51") (name "unconnected-(U1A-PB0{slash}SPI_SS{slash}EXINT_PCINT0-Pad8)") (class "Default")
      (node (ref "U1") (pin "8") (pinfunction "PB0/SPI_SS/EXINT_PCINT0_8") (pintype "passive"))
    )
    (net (code "52") (name "unconnected-(U1A-PB7{slash}USART1_RTS{slash}TC0_OCA{slash}TC1_OCC{slash}EXINT_PCINT7-Pad12)") (class "Default")
      (node (ref "U1") (pin "12") (pinfunction "PB7/USART1_RTS/TC0_OCA/TC1_OCC/EXINT_PCINT7_12") (pintype "passive"))
    )
    (net (code "53") (name "unconnected-(U1A-PC7{slash}TC3_ICP{slash}TC4_OCA{slash}CPU_CLK0-Pad32)") (class "Default")
      (node (ref "U1") (pin "32") (pinfunction "PC7/TC3_ICP/TC4_OCA/CPU_CLK0_32") (pintype "passive"))
    )
    (net (code "54") (name "unconnected-(U1A-PD2{slash}USART1_RXD{slash}EXINT_INT2-Pad20)") (class "Default")
      (node (ref "U1") (pin "20") (pinfunction "PD2/USART1_RXD/EXINT_INT2_20") (pintype "passive"))
    )
    (net (code "55") (name "unconnected-(U1A-PD3{slash}USART1_TXD{slash}EXINT_INT3-Pad21)") (class "Default")
      (node (ref "U1") (pin "21") (pinfunction "PD3/USART1_TXD/EXINT_INT3_21") (pintype "passive"))
    )
    (net (code "56") (name "unconnected-(U1A-PD5{slash}USART1_XCK{slash}USART1_CTS-Pad22)") (class "Default")
      (node (ref "U1") (pin "22") (pinfunction "PD5/USART1_XCK/USART1_CTS_22") (pintype "passive"))
    )
    (net (code "57") (name "unconnected-(U1A-PE6{slash}EXINT_INT6{slash}AC_AIN0-Pad1)") (class "Default")
      (node (ref "U1") (pin "1") (pinfunction "PE6/EXINT_INT6/AC_AIN0_1") (pintype "passive+no_connect"))
    )
    (net (code "58") (name "unconnected-(U1B-PF0{slash}ADC_0-Pad41)") (class "Default")
      (node (ref "U1") (pin "41") (pinfunction "PF0/ADC_0_41") (pintype "passive"))
    )
    (net (code "59") (name "unconnected-(U1B-PF1{slash}ADC_1-Pad40)") (class "Default")
      (node (ref "U1") (pin "40") (pinfunction "PF1/ADC_1_40") (pintype "passive"))
    )
  )
)
